# DAC_SPI.net
KiCad netlist of a schematic drawn in Altium Designer
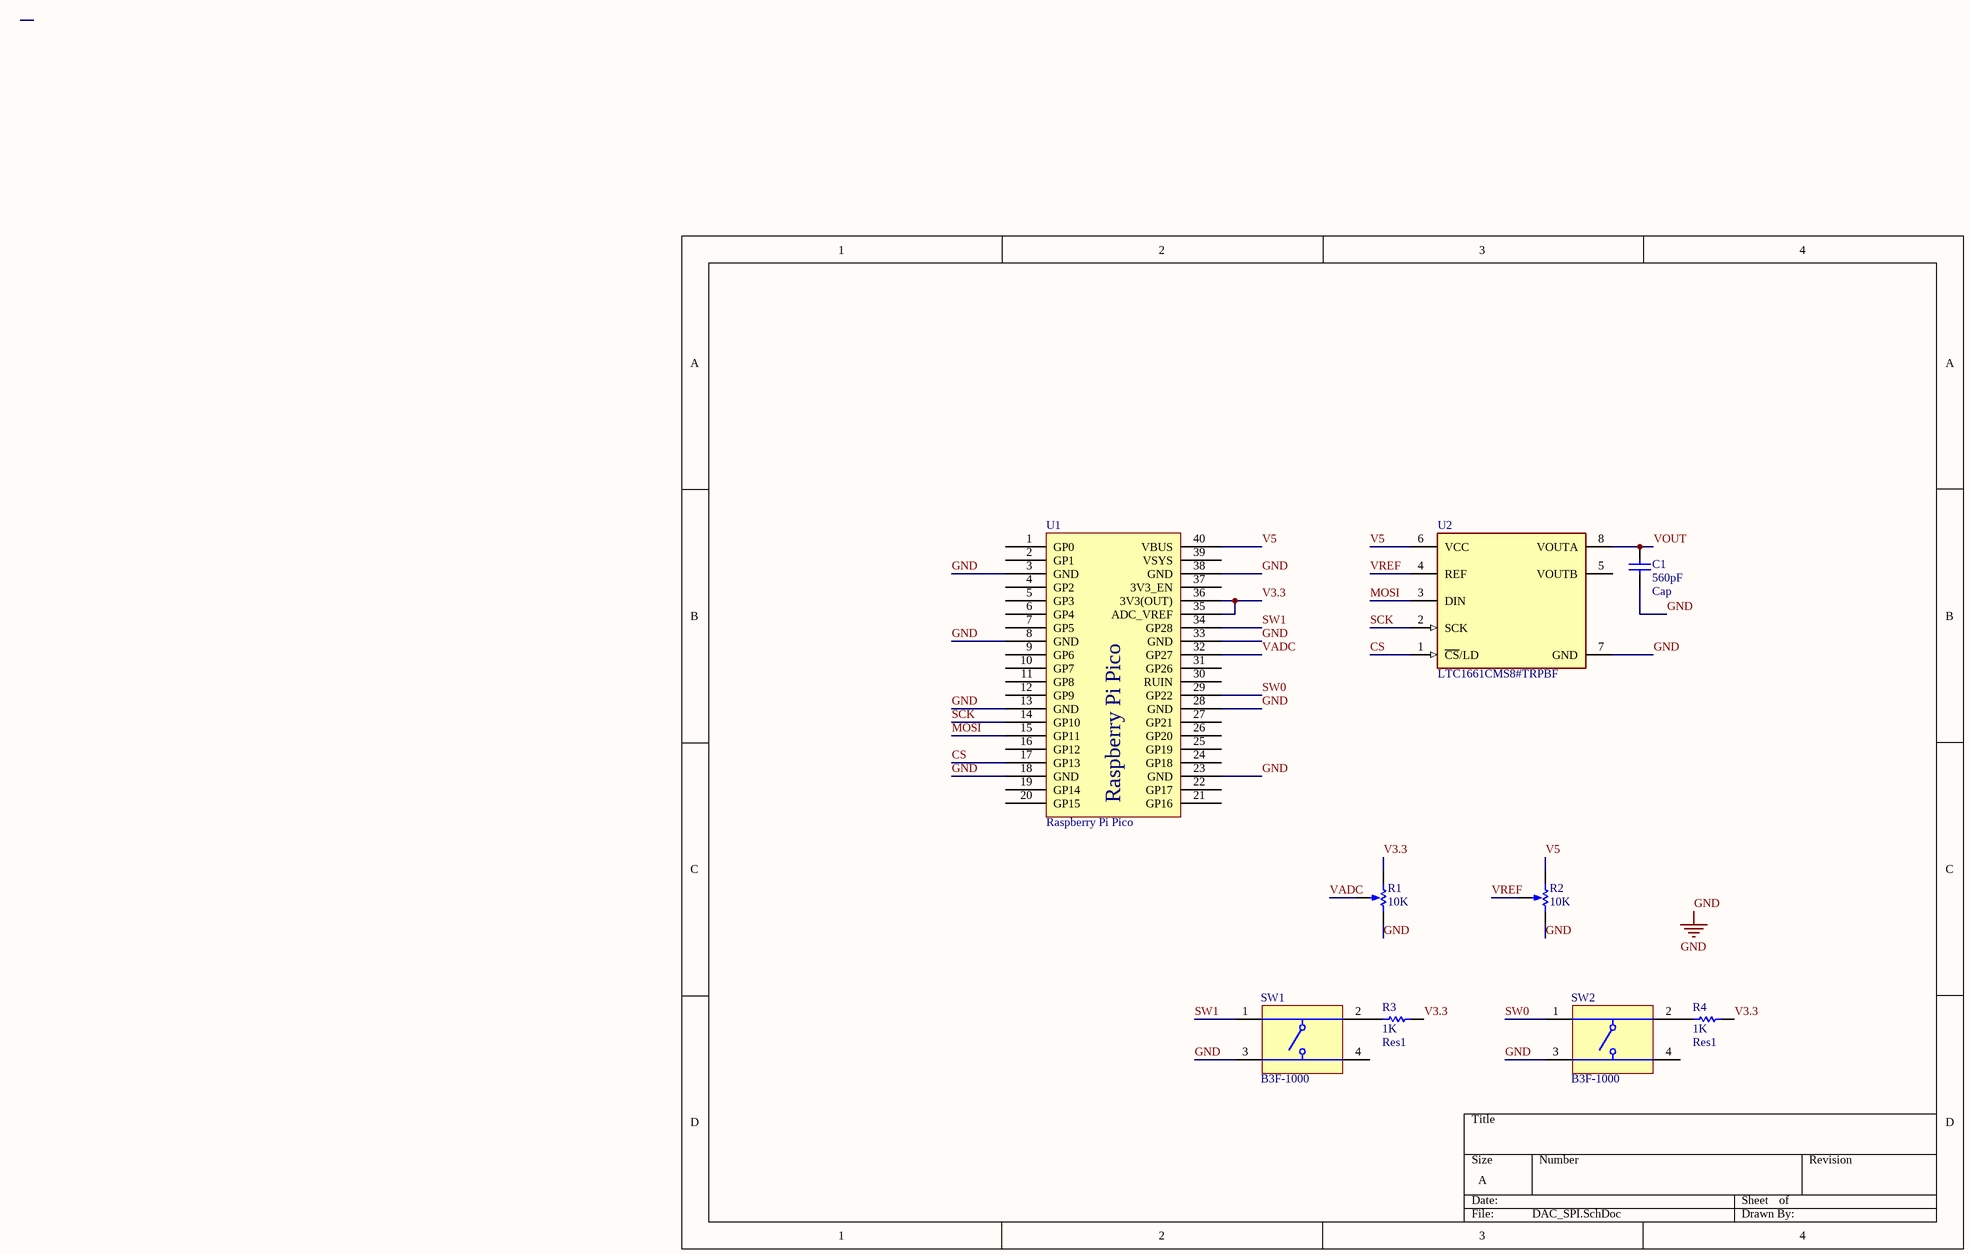
[diagram p0: DAC_SPI.SchDoc]

(export (version "E")
  (design (tool "Eeschema 10.0.6"))
  (components
    (comp (ref "C1")
      (value "Cap")
      (footprint "RAD-0.3")
      (description "Capacitor")
      (fields (field (name "ALTIUM_VALUE") "560pF") (field (name "PUBLISHER") "Altium Limited"))
      (libsource (lib "Miscellaneous Devices") (part "Cap"))
    )
    (comp (ref "R1")
      (value "10K")
      (footprint "POT inline wide")
      (description "Potentiometer")
      (fields (field (name "Comment") "RPot_1") (field (name "PUBLISHER") "Altium Limited"))
      (libsource (lib "ECE Lib 22") (part "RPot_3"))
    )
    (comp (ref "R2")
      (value "10K")
      (footprint "POT inline wide")
      (description "Potentiometer")
      (fields (field (name "Comment") "RPot_1") (field (name "PUBLISHER") "Altium Limited"))
      (libsource (lib "ECE Lib 22") (part "RPot_3"))
    )
    (comp (ref "R3")
      (value "Res1")
      (footprint "AXIAL-0.3")
      (description "Resistor")
      (fields (field (name "ALTIUM_VALUE") "1K") (field (name "PUBLISHER") "Altium Limited"))
      (libsource (lib "Miscellaneous Devices") (part "Res1"))
    )
    (comp (ref "R4")
      (value "Res1")
      (footprint "AXIAL-0.3")
      (description "Resistor")
      (fields (field (name "ALTIUM_VALUE") "1K") (field (name "PUBLISHER") "Altium Limited"))
      (libsource (lib "Miscellaneous Devices") (part "Res1"))
    )
    (comp (ref "SW1")
      (value "B3F-1000")
      (footprint "OMRON-B3F-1000-4_V")
      (description "Tactile Switch, SPST-NO, 0.05 A, 5 to 24 V, -25 to 70 degC, 4-Pin THD, RoHS, Bulk")
      (libsource (lib "switch") (part "CMP-1677-00002-1"))
    )
    (comp (ref "SW2")
      (value "B3F-1000")
      (footprint "OMRON-B3F-1000-4_V")
      (description "Tactile Switch, SPST-NO, 0.05 A, 5 to 24 V, -25 to 70 degC, 4-Pin THD, RoHS, Bulk")
      (libsource (lib "switch") (part "CMP-1677-00002-1"))
    )
    (comp (ref "U1")
      (value "Raspberry Pi Pico")
      (footprint "Raspberry Pi Pico")
      (libsource (lib "ECE Lib 22") (part "Raspberry Pi Pico"))
    )
    (comp (ref "U2")
      (value "LTC1661CMS8#TRPBF")
      (footprint "FP-MS8-8-05-08-1660-IPC_A")
      (description "IC DAC 10BIT V-OUT 8MSOP")
      (libsource (lib "Components - 08.03.26 - 23.20") (part "CMP-09082-000102-1"))
    )
  )
  (nets
    (net (code "1") (name "/CS") (class "Default")
      (node (ref "U1") (pin "17") (pinfunction "GP13_17") (pintype "passive"))
      (node (ref "U2") (pin "1") (pinfunction "~{CS}/LD_1") (pintype "input"))
    )
    (net (code "2") (name "/MOSI") (class "Default")
      (node (ref "U1") (pin "15") (pinfunction "GP11_15") (pintype "passive"))
      (node (ref "U2") (pin "3") (pinfunction "DIN_3") (pintype "power_in"))
    )
    (net (code "3") (name "/SCK") (class "Default")
      (node (ref "U1") (pin "14") (pinfunction "GP10_14") (pintype "passive"))
      (node (ref "U2") (pin "2") (pinfunction "SCK_2") (pintype "input"))
    )
    (net (code "4") (name "/SW0") (class "Default")
      (node (ref "SW2") (pin "1") (pinfunction "1_1") (pintype "passive"))
      (node (ref "U1") (pin "29") (pinfunction "GP22_29") (pintype "passive"))
    )
    (net (code "5") (name "/SW1") (class "Default")
      (node (ref "SW1") (pin "1") (pinfunction "1_1") (pintype "passive"))
      (node (ref "U1") (pin "34") (pinfunction "GP28_34") (pintype "passive"))
    )
    (net (code "6") (name "/V3.3") (class "Default")
      (node (ref "R1") (pin "1") (pinfunction "TOP_1") (pintype "passive"))
      (node (ref "R3") (pin "2") (pinfunction "2_2") (pintype "passive"))
      (node (ref "R4") (pin "2") (pinfunction "2_2") (pintype "passive"))
      (node (ref "U1") (pin "35") (pinfunction "ADC_VREF_35") (pintype "passive"))
      (node (ref "U1") (pin "36") (pinfunction "3V3(OUT)_36") (pintype "passive"))
    )
    (net (code "7") (name "/V5") (class "Default")
      (node (ref "R2") (pin "1") (pinfunction "TOP_1") (pintype "passive"))
      (node (ref "U1") (pin "40") (pinfunction "VBUS_40") (pintype "passive"))
      (node (ref "U2") (pin "6") (pinfunction "VCC_6") (pintype "power_in"))
    )
    (net (code "8") (name "/VADC") (class "Default")
      (node (ref "R1") (pin "2") (pinfunction "TAP_2") (pintype "passive"))
      (node (ref "U1") (pin "32") (pinfunction "GP27_32") (pintype "passive"))
    )
    (net (code "9") (name "/VOUT") (class "Default")
      (node (ref "C1") (pin "2") (pinfunction "2_2") (pintype "passive"))
      (node (ref "U2") (pin "8") (pinfunction "VOUTA_8") (pintype "power_in"))
    )
    (net (code "10") (name "/VREF") (class "Default")
      (node (ref "R2") (pin "2") (pinfunction "TAP_2") (pintype "passive"))
      (node (ref "U2") (pin "4") (pinfunction "REF_4") (pintype "passive"))
    )
    (net (code "11") (name "GND") (class "Default")
      (node (ref "C1") (pin "1") (pinfunction "1_1") (pintype "passive"))
      (node (ref "R1") (pin "3") (pinfunction "BOT_3") (pintype "passive"))
      (node (ref "R2") (pin "3") (pinfunction "BOT_3") (pintype "passive"))
      (node (ref "SW1") (pin "3") (pinfunction "3_3") (pintype "passive"))
      (node (ref "SW2") (pin "3") (pinfunction "3_3") (pintype "passive"))
      (node (ref "U1") (pin "13") (pinfunction "GND_13") (pintype "passive"))
      (node (ref "U1") (pin "18") (pinfunction "GND_18") (pintype "passive"))
      (node (ref "U1") (pin "23") (pinfunction "GND_23") (pintype "passive"))
      (node (ref "U1") (pin "28") (pinfunction "GND_28") (pintype "passive"))
      (node (ref "U1") (pin "3") (pinfunction "GND_3") (pintype "passive"))
      (node (ref "U1") (pin "33") (pinfunction "GND_33") (pintype "passive"))
      (node (ref "U1") (pin "38") (pinfunction "GND_38") (pintype "passive"))
      (node (ref "U1") (pin "8") (pinfunction "GND_8") (pintype "passive"))
      (node (ref "U2") (pin "7") (pinfunction "GND_7") (pintype "power_in"))
    )
    (net (code "12") (name "Net-(R3-Pad1)") (class "Default")
      (node (ref "R3") (pin "1") (pinfunction "1_1") (pintype "passive"))
      (node (ref "SW1") (pin "2") (pinfunction "2_2") (pintype "passive"))
    )
    (net (code "13") (name "Net-(R4-Pad1)") (class "Default")
      (node (ref "R4") (pin "1") (pinfunction "1_1") (pintype "passive"))
      (node (ref "SW2") (pin "2") (pinfunction "2_2") (pintype "passive"))
    )
    (net (code "14") (name "unconnected-(SW1-Pad4)") (class "Default")
      (node (ref "SW1") (pin "4") (pinfunction "4_4") (pintype "passive"))
    )
    (net (code "15") (name "unconnected-(SW2-Pad4)") (class "Default")
      (node (ref "SW2") (pin "4") (pinfunction "4_4") (pintype "passive"))
    )
    (net (code "16") (name "unconnected-(U1-3V3_EN-Pad37)") (class "Default")
      (node (ref "U1") (pin "37") (pinfunction "3V3_EN_37") (pintype "passive"))
    )
    (net (code "17") (name "unconnected-(U1-GP0-Pad1)") (class "Default")
      (node (ref "U1") (pin "1") (pinfunction "GP0_1") (pintype "passive"))
    )
    (net (code "18") (name "unconnected-(U1-GP1-Pad2)") (class "Default")
      (node (ref "U1") (pin "2") (pinfunction "GP1_2") (pintype "passive"))
    )
    (net (code "19") (name "unconnected-(U1-GP2-Pad4)") (class "Default")
      (node (ref "U1") (pin "4") (pinfunction "GP2_4") (pintype "passive"))
    )
    (net (code "20") (name "unconnected-(U1-GP3-Pad5)") (class "Default")
      (node (ref "U1") (pin "5") (pinfunction "GP3_5") (pintype "passive"))
    )
    (net (code "21") (name "unconnected-(U1-GP4-Pad6)") (class "Default")
      (node (ref "U1") (pin "6") (pinfunction "GP4_6") (pintype "passive"))
    )
    (net (code "22") (name "unconnected-(U1-GP5-Pad7)") (class "Default")
      (node (ref "U1") (pin "7") (pinfunction "GP5_7") (pintype "passive"))
    )
    (net (code "23") (name "unconnected-(U1-GP6-Pad9)") (class "Default")
      (node (ref "U1") (pin "9") (pinfunction "GP6_9") (pintype "passive"))
    )
    (net (code "24") (name "unconnected-(U1-GP7-Pad10)") (class "Default")
      (node (ref "U1") (pin "10") (pinfunction "GP7_10") (pintype "passive"))
    )
    (net (code "25") (name "unconnected-(U1-GP8-Pad11)") (class "Default")
      (node (ref "U1") (pin "11") (pinfunction "GP8_11") (pintype "passive"))
    )
    (net (code "26") (name "unconnected-(U1-GP9-Pad12)") (class "Default")
      (node (ref "U1") (pin "12") (pinfunction "GP9_12") (pintype "passive"))
    )
    (net (code "27") (name "unconnected-(U1-GP12-Pad16)") (class "Default")
      (node (ref "U1") (pin "16") (pinfunction "GP12_16") (pintype "passive"))
    )
    (net (code "28") (name "unconnected-(U1-GP14-Pad19)") (class "Default")
      (node (ref "U1") (pin "19") (pinfunction "GP14_19") (pintype "passive"))
    )
    (net (code "29") (name "unconnected-(U1-GP15-Pad20)") (class "Default")
      (node (ref "U1") (pin "20") (pinfunction "GP15_20") (pintype "passive"))
    )
    (net (code "30") (name "unconnected-(U1-GP16-Pad21)") (class "Default")
      (node (ref "U1") (pin "21") (pinfunction "GP16_21") (pintype "passive"))
    )
    (net (code "31") (name "unconnected-(U1-GP17-Pad22)") (class "Default")
      (node (ref "U1") (pin "22") (pinfunction "GP17_22") (pintype "passive"))
    )
    (net (code "32") (name "unconnected-(U1-GP18-Pad24)") (class "Default")
      (node (ref "U1") (pin "24") (pinfunction "GP18_24") (pintype "passive"))
    )
    (net (code "33") (name "unconnected-(U1-GP19-Pad25)") (class "Default")
      (node (ref "U1") (pin "25") (pinfunction "GP19_25") (pintype "passive"))
    )
    (net (code "34") (name "unconnected-(U1-GP20-Pad26)") (class "Default")
      (node (ref "U1") (pin "26") (pinfunction "GP20_26") (pintype "passive"))
    )
    (net (code "35") (name "unconnected-(U1-GP21-Pad27)") (class "Default")
      (node (ref "U1") (pin "27") (pinfunction "GP21_27") (pintype "passive"))
    )
    (net (code "36") (name "unconnected-(U1-GP26-Pad31)") (class "Default")
      (node (ref "U1") (pin "31") (pinfunction "GP26_31") (pintype "passive"))
    )
    (net (code "37") (name "unconnected-(U1-RUIN-Pad30)") (class "Default")
      (node (ref "U1") (pin "30") (pinfunction "RUIN_30") (pintype "passive"))
    )
    (net (code "38") (name "unconnected-(U1-VSYS-Pad39)") (class "Default")
      (node (ref "U1") (pin "39") (pinfunction "VSYS_39") (pintype "passive"))
    )
    (net (code "39") (name "unconnected-(U2-VOUTB-Pad5)") (class "Default")
      (node (ref "U2") (pin "5") (pinfunction "VOUTB_5") (pintype "power_in"))
    )
  )
)
